# SiNEProduction.net
KiCad netlist of a schematic drawn in EAGLE
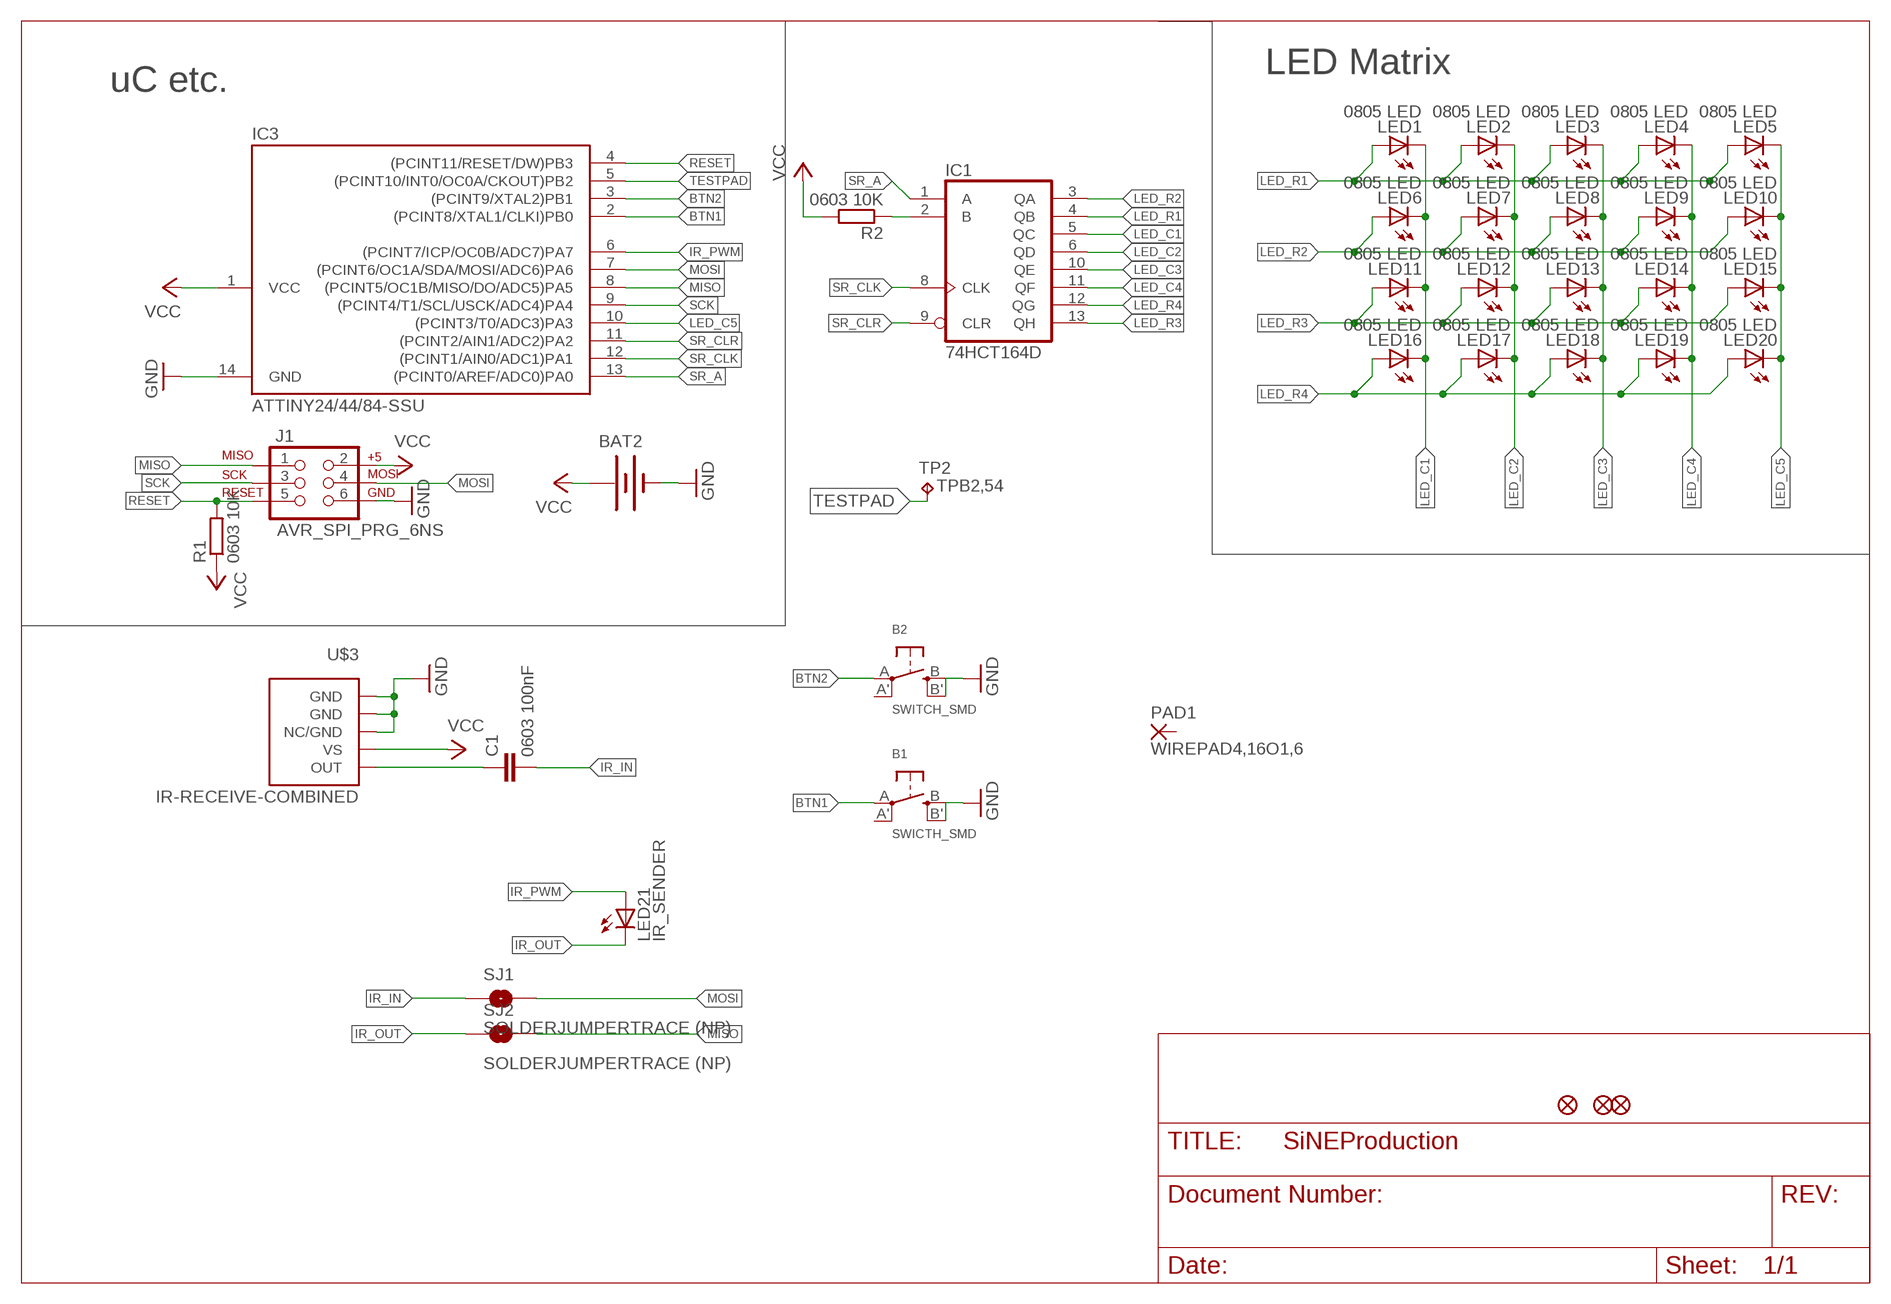
[diagram p0: schematic, sheet 1]

(export (version "E")
  (design (tool "Eeschema 10.0.6"))
  (components
    (comp (ref "B1")
      (value "SWICTH_SMD")
      (footprint "eagle-import:EVQ-Q2")
      (libsource (lib "eagle-import") (part "SWITCH_TACT_SMT"))
    )
    (comp (ref "B2")
      (value "SWITCH_SMD")
      (footprint "eagle-import:EVQ-Q2")
      (libsource (lib "eagle-import") (part "SWITCH_TACT_SMT"))
    )
    (comp (ref "BAT2")
      (value "BATTERY20SMD")
      (footprint "eagle-import:BATTCON_20MM")
      (libsource (lib "eagle-import") (part "BATTERY20SMD"))
    )
    (comp (ref "C1")
      (value "0603 100nF")
      (footprint "eagle-import:C0805")
      (libsource (lib "eagle-import") (part "C-EUC0805"))
    )
    (comp (ref "IC1")
      (value "74HCT164D")
      (footprint "eagle-import:SO14")
      (libsource (lib "eagle-import") (part "74164DHCT"))
    )
    (comp (ref "IC3")
      (value "ATTINY24/44/84-SSU")
      (footprint "eagle-import:SOIC14")
      (libsource (lib "eagle-import") (part "ATTINY24/44/84-SSU"))
    )
    (comp (ref "J1")
      (value "AVR_SPI_PRG_6NS")
      (footprint "eagle-import:2X3-NS")
      (libsource (lib "eagle-import") (part "AVR_SPI_PRG_6NS"))
    )
    (comp (ref "JP1")
      (value "FIDUCIAL1X2.5-STOP")
      (footprint "eagle-import:FIDUCIAL-1X2.5-STOP")
      (libsource (lib "eagle-import") (part "FIDUCIAL1X2.5-STOP"))
    )
    (comp (ref "JP2")
      (value "FIDUCIAL1X2.5-STOP")
      (footprint "eagle-import:FIDUCIAL-1X2.5-STOP")
      (libsource (lib "eagle-import") (part "FIDUCIAL1X2.5-STOP"))
    )
    (comp (ref "JP3")
      (value "FIDUCIAL1X2.5-STOP")
      (footprint "eagle-import:FIDUCIAL-1X2.5-STOP")
      (libsource (lib "eagle-import") (part "FIDUCIAL1X2.5-STOP"))
    )
    (comp (ref "LED1")
      (value "0805 LED")
      (footprint "eagle-import:CHIPLED_0805")
      (libsource (lib "eagle-import") (part "LEDCHIPLED_0805"))
    )
    (comp (ref "LED2")
      (value "0805 LED")
      (footprint "eagle-import:CHIPLED_0805")
      (libsource (lib "eagle-import") (part "LEDCHIPLED_0805"))
    )
    (comp (ref "LED3")
      (value "0805 LED")
      (footprint "eagle-import:CHIPLED_0805")
      (libsource (lib "eagle-import") (part "LEDCHIPLED_0805"))
    )
    (comp (ref "LED4")
      (value "0805 LED")
      (footprint "eagle-import:CHIPLED_0805")
      (libsource (lib "eagle-import") (part "LEDCHIPLED_0805"))
    )
    (comp (ref "LED5")
      (value "0805 LED")
      (footprint "eagle-import:CHIPLED_0805")
      (libsource (lib "eagle-import") (part "LEDCHIPLED_0805"))
    )
    (comp (ref "LED6")
      (value "0805 LED")
      (footprint "eagle-import:CHIPLED_0805")
      (libsource (lib "eagle-import") (part "LEDCHIPLED_0805"))
    )
    (comp (ref "LED7")
      (value "0805 LED")
      (footprint "eagle-import:CHIPLED_0805")
      (libsource (lib "eagle-import") (part "LEDCHIPLED_0805"))
    )
    (comp (ref "LED8")
      (value "0805 LED")
      (footprint "eagle-import:CHIPLED_0805")
      (libsource (lib "eagle-import") (part "LEDCHIPLED_0805"))
    )
    (comp (ref "LED9")
      (value "0805 LED")
      (footprint "eagle-import:CHIPLED_0805")
      (libsource (lib "eagle-import") (part "LEDCHIPLED_0805"))
    )
    (comp (ref "LED10")
      (value "0805 LED")
      (footprint "eagle-import:CHIPLED_0805")
      (libsource (lib "eagle-import") (part "LEDCHIPLED_0805"))
    )
    (comp (ref "LED11")
      (value "0805 LED")
      (footprint "eagle-import:CHIPLED_0805")
      (libsource (lib "eagle-import") (part "LEDCHIPLED_0805"))
    )
    (comp (ref "LED12")
      (value "0805 LED")
      (footprint "eagle-import:CHIPLED_0805")
      (libsource (lib "eagle-import") (part "LEDCHIPLED_0805"))
    )
    (comp (ref "LED13")
      (value "0805 LED")
      (footprint "eagle-import:CHIPLED_0805")
      (libsource (lib "eagle-import") (part "LEDCHIPLED_0805"))
    )
    (comp (ref "LED14")
      (value "0805 LED")
      (footprint "eagle-import:CHIPLED_0805")
      (libsource (lib "eagle-import") (part "LEDCHIPLED_0805"))
    )
    (comp (ref "LED15")
      (value "0805 LED")
      (footprint "eagle-import:CHIPLED_0805")
      (libsource (lib "eagle-import") (part "LEDCHIPLED_0805"))
    )
    (comp (ref "LED16")
      (value "0805 LED")
      (footprint "eagle-import:CHIPLED_0805")
      (libsource (lib "eagle-import") (part "LEDCHIPLED_0805"))
    )
    (comp (ref "LED17")
      (value "0805 LED")
      (footprint "eagle-import:CHIPLED_0805")
      (libsource (lib "eagle-import") (part "LEDCHIPLED_0805"))
    )
    (comp (ref "LED18")
      (value "0805 LED")
      (footprint "eagle-import:CHIPLED_0805")
      (libsource (lib "eagle-import") (part "LEDCHIPLED_0805"))
    )
    (comp (ref "LED19")
      (value "0805 LED")
      (footprint "eagle-import:CHIPLED_0805")
      (libsource (lib "eagle-import") (part "LEDCHIPLED_0805"))
    )
    (comp (ref "LED20")
      (value "0805 LED")
      (footprint "eagle-import:CHIPLED_0805")
      (libsource (lib "eagle-import") (part "LEDCHIPLED_0805"))
    )
    (comp (ref "LED21")
      (value "IR_SENDER")
      (footprint "eagle-import:CHIPLED_1206")
      (libsource (lib "eagle-import") (part "led_LEDCHIPLED_1206"))
    )
    (comp (ref "PAD1")
      (value "WIREPAD4,16O1,6")
      (footprint "eagle-import:4,16O1,6")
      (libsource (lib "eagle-import") (part "WIREPAD4,16O1,6"))
    )
    (comp (ref "R1")
      (value "0603 10K")
      (footprint "eagle-import:R0805")
      (libsource (lib "eagle-import") (part "R-EU_R0805"))
    )
    (comp (ref "R2")
      (value "0603 10K")
      (footprint "eagle-import:R0805")
      (libsource (lib "eagle-import") (part "R-EU_R0805"))
    )
    (comp (ref "SJ1")
      (value "SOLDERJUMPERTRACE (NP)")
      (footprint "eagle-import:SJ_2S-TRACE")
      (libsource (lib "eagle-import") (part "SOLDERJUMPERTRACE"))
    )
    (comp (ref "SJ2")
      (value "SOLDERJUMPERTRACE (NP)")
      (footprint "eagle-import:SJ_2S-TRACE")
      (libsource (lib "eagle-import") (part "SOLDERJUMPERTRACE"))
    )
    (comp (ref "TP2")
      (value "TPB2,54")
      (footprint "eagle-import:B2,54")
      (libsource (lib "eagle-import") (part "TPB2,54"))
    )
    (comp (ref "U$3")
      (value "IR-RECEIVE-COMBINED")
      (footprint "eagle-import:TSOP-COMBINED")
      (libsource (lib "eagle-import") (part "IR-RECEIVE-COMBINED"))
    )
  )
  (nets
    (net (code "1") (name "BTN1") (class "Default")
      (node (ref "B1") (pin "A") (pinfunction "P_A") (pintype "passive"))
      (node (ref "IC3") (pin "2") (pinfunction "(PCINT8/XTAL1/CLKI)PB0_2") (pintype "bidirectional"))
    )
    (net (code "2") (name "BTN2") (class "Default")
      (node (ref "B2") (pin "A") (pinfunction "P_A") (pintype "passive"))
      (node (ref "IC3") (pin "3") (pinfunction "(PCINT9/XTAL2)PB1_3") (pintype "bidirectional"))
    )
    (net (code "3") (name "GND") (class "Default")
      (node (ref "B1") (pin "B") (pinfunction "S_B") (pintype "passive"))
      (node (ref "B1") (pin "B'") (pinfunction "S1_B'") (pintype "passive"))
      (node (ref "B2") (pin "B") (pinfunction "S_B") (pintype "passive"))
      (node (ref "B2") (pin "B'") (pinfunction "S1_B'") (pintype "passive"))
      (node (ref "BAT2") (pin "2") (pinfunction "-_2") (pintype "power_in"))
      (node (ref "IC3") (pin "14") (pinfunction "GND_14") (pintype "power_in"))
      (node (ref "J1") (pin "6") (pinfunction "6_6") (pintype "passive"))
      (node (ref "U$3") (pin "1") (pinfunction "GND_1") (pintype "bidirectional"))
      (node (ref "U$3") (pin "2") (pinfunction "NC/GND_2") (pintype "bidirectional"))
      (node (ref "U$3") (pin "5") (pinfunction "GND_5") (pintype "bidirectional"))
    )
    (net (code "4") (name "IR_IN") (class "Default")
      (node (ref "C1") (pin "2") (pinfunction "2_2") (pintype "passive"))
      (node (ref "SJ1") (pin "1") (pinfunction "1_1") (pintype "passive"))
    )
    (net (code "5") (name "IR_OUT") (class "Default")
      (node (ref "LED21") (pin "C") (pinfunction "C_C") (pintype "passive"))
      (node (ref "SJ2") (pin "1") (pinfunction "1_1") (pintype "passive"))
    )
    (net (code "6") (name "IR_PWM") (class "Default")
      (node (ref "IC3") (pin "6") (pinfunction "(PCINT7/ICP/OC0B/ADC7)PA7_6") (pintype "bidirectional"))
      (node (ref "LED21") (pin "A") (pinfunction "A_A") (pintype "passive"))
    )
    (net (code "7") (name "LED_C1") (class "Default")
      (node (ref "IC1") (pin "5") (pinfunction "QC_5") (pintype "output"))
      (node (ref "LED1") (pin "C") (pinfunction "C_C") (pintype "passive"))
      (node (ref "LED11") (pin "C") (pinfunction "C_C") (pintype "passive"))
      (node (ref "LED16") (pin "C") (pinfunction "C_C") (pintype "passive"))
      (node (ref "LED6") (pin "C") (pinfunction "C_C") (pintype "passive"))
    )
    (net (code "8") (name "LED_C2") (class "Default")
      (node (ref "IC1") (pin "6") (pinfunction "QD_6") (pintype "output"))
      (node (ref "LED12") (pin "C") (pinfunction "C_C") (pintype "passive"))
      (node (ref "LED17") (pin "C") (pinfunction "C_C") (pintype "passive"))
      (node (ref "LED2") (pin "C") (pinfunction "C_C") (pintype "passive"))
      (node (ref "LED7") (pin "C") (pinfunction "C_C") (pintype "passive"))
    )
    (net (code "9") (name "LED_C3") (class "Default")
      (node (ref "IC1") (pin "10") (pinfunction "QE_10") (pintype "output"))
      (node (ref "LED13") (pin "C") (pinfunction "C_C") (pintype "passive"))
      (node (ref "LED18") (pin "C") (pinfunction "C_C") (pintype "passive"))
      (node (ref "LED3") (pin "C") (pinfunction "C_C") (pintype "passive"))
      (node (ref "LED8") (pin "C") (pinfunction "C_C") (pintype "passive"))
    )
    (net (code "10") (name "LED_C4") (class "Default")
      (node (ref "IC1") (pin "11") (pinfunction "QF_11") (pintype "output"))
      (node (ref "LED14") (pin "C") (pinfunction "C_C") (pintype "passive"))
      (node (ref "LED19") (pin "C") (pinfunction "C_C") (pintype "passive"))
      (node (ref "LED4") (pin "C") (pinfunction "C_C") (pintype "passive"))
      (node (ref "LED9") (pin "C") (pinfunction "C_C") (pintype "passive"))
    )
    (net (code "11") (name "LED_C5") (class "Default")
      (node (ref "IC3") (pin "10") (pinfunction "(PCINT3/T0/ADC3)PA3_10") (pintype "bidirectional"))
      (node (ref "LED10") (pin "C") (pinfunction "C_C") (pintype "passive"))
      (node (ref "LED15") (pin "C") (pinfunction "C_C") (pintype "passive"))
      (node (ref "LED20") (pin "C") (pinfunction "C_C") (pintype "passive"))
      (node (ref "LED5") (pin "C") (pinfunction "C_C") (pintype "passive"))
    )
    (net (code "12") (name "LED_R1") (class "Default")
      (node (ref "IC1") (pin "4") (pinfunction "QB_4") (pintype "output"))
      (node (ref "LED1") (pin "A") (pinfunction "A_A") (pintype "passive"))
      (node (ref "LED2") (pin "A") (pinfunction "A_A") (pintype "passive"))
      (node (ref "LED3") (pin "A") (pinfunction "A_A") (pintype "passive"))
      (node (ref "LED4") (pin "A") (pinfunction "A_A") (pintype "passive"))
      (node (ref "LED5") (pin "A") (pinfunction "A_A") (pintype "passive"))
    )
    (net (code "13") (name "LED_R2") (class "Default")
      (node (ref "IC1") (pin "3") (pinfunction "QA_3") (pintype "output"))
      (node (ref "LED10") (pin "A") (pinfunction "A_A") (pintype "passive"))
      (node (ref "LED6") (pin "A") (pinfunction "A_A") (pintype "passive"))
      (node (ref "LED7") (pin "A") (pinfunction "A_A") (pintype "passive"))
      (node (ref "LED8") (pin "A") (pinfunction "A_A") (pintype "passive"))
      (node (ref "LED9") (pin "A") (pinfunction "A_A") (pintype "passive"))
    )
    (net (code "14") (name "LED_R3") (class "Default")
      (node (ref "IC1") (pin "13") (pinfunction "QH_13") (pintype "output"))
      (node (ref "LED11") (pin "A") (pinfunction "A_A") (pintype "passive"))
      (node (ref "LED12") (pin "A") (pinfunction "A_A") (pintype "passive"))
      (node (ref "LED13") (pin "A") (pinfunction "A_A") (pintype "passive"))
      (node (ref "LED14") (pin "A") (pinfunction "A_A") (pintype "passive"))
      (node (ref "LED15") (pin "A") (pinfunction "A_A") (pintype "passive"))
    )
    (net (code "15") (name "LED_R4") (class "Default")
      (node (ref "IC1") (pin "12") (pinfunction "QG_12") (pintype "output"))
      (node (ref "LED16") (pin "A") (pinfunction "A_A") (pintype "passive"))
      (node (ref "LED17") (pin "A") (pinfunction "A_A") (pintype "passive"))
      (node (ref "LED18") (pin "A") (pinfunction "A_A") (pintype "passive"))
      (node (ref "LED19") (pin "A") (pinfunction "A_A") (pintype "passive"))
      (node (ref "LED20") (pin "A") (pinfunction "A_A") (pintype "passive"))
    )
    (net (code "16") (name "MISO") (class "Default")
      (node (ref "IC3") (pin "8") (pinfunction "(PCINT5/OC1B/MISO/DO/ADC5)PA5_8") (pintype "bidirectional"))
      (node (ref "J1") (pin "1") (pinfunction "1_1") (pintype "passive"))
      (node (ref "SJ2") (pin "2") (pinfunction "2_2") (pintype "passive"))
    )
    (net (code "17") (name "MOSI") (class "Default")
      (node (ref "IC3") (pin "7") (pinfunction "(PCINT6/OC1A/SDA/MOSI/ADC6)PA6_7") (pintype "bidirectional"))
      (node (ref "J1") (pin "4") (pinfunction "4_4") (pintype "passive"))
      (node (ref "SJ1") (pin "2") (pinfunction "2_2") (pintype "passive"))
    )
    (net (code "18") (name "Net-(IC1A-B)") (class "Default")
      (node (ref "IC1") (pin "2") (pinfunction "B_2") (pintype "input"))
      (node (ref "R2") (pin "1") (pinfunction "1_1") (pintype "passive"))
    )
    (net (code "19") (name "Net-(U$3-OUT)") (class "Default")
      (node (ref "C1") (pin "1") (pinfunction "1_1") (pintype "passive"))
      (node (ref "U$3") (pin "4") (pinfunction "OUT_4") (pintype "bidirectional"))
    )
    (net (code "20") (name "RESET") (class "Default")
      (node (ref "IC3") (pin "4") (pinfunction "(PCINT11/RESET/DW)PB3_4") (pintype "bidirectional"))
      (node (ref "J1") (pin "5") (pinfunction "5_5") (pintype "passive"))
      (node (ref "R1") (pin "2") (pinfunction "2_2") (pintype "passive"))
    )
    (net (code "21") (name "SCK") (class "Default")
      (node (ref "IC3") (pin "9") (pinfunction "(PCINT4/T1/SCL/USCK/ADC4)PA4_9") (pintype "bidirectional"))
      (node (ref "J1") (pin "3") (pinfunction "3_3") (pintype "passive"))
    )
    (net (code "22") (name "SR_A") (class "Default")
      (node (ref "IC1") (pin "1") (pinfunction "A_1") (pintype "input"))
      (node (ref "IC3") (pin "13") (pinfunction "(PCINT0/AREF/ADC0)PA0_13") (pintype "bidirectional"))
    )
    (net (code "23") (name "SR_CLK") (class "Default")
      (node (ref "IC1") (pin "8") (pinfunction "CLK_8") (pintype "input"))
      (node (ref "IC3") (pin "12") (pinfunction "(PCINT1/AIN0/ADC1)PA1_12") (pintype "bidirectional"))
    )
    (net (code "24") (name "SR_CLR") (class "Default")
      (node (ref "IC1") (pin "9") (pinfunction "CLR_9") (pintype "input"))
      (node (ref "IC3") (pin "11") (pinfunction "(PCINT2/AIN1/ADC2)PA2_11") (pintype "bidirectional"))
    )
    (net (code "25") (name "TESTPAD") (class "Default")
      (node (ref "IC3") (pin "5") (pinfunction "(PCINT10/INT0/OC0A/CKOUT)PB2_5") (pintype "bidirectional"))
      (node (ref "TP2") (pin "TP") (pinfunction "TP_TP") (pintype "input"))
    )
    (net (code "26") (name "VCC") (class "Default")
      (node (ref "BAT2") (pin "1") (pinfunction "+_1") (pintype "power_in"))
      (node (ref "IC3") (pin "1") (pinfunction "VCC_1") (pintype "power_in"))
      (node (ref "J1") (pin "2") (pinfunction "2_2") (pintype "passive"))
      (node (ref "R1") (pin "1") (pinfunction "1_1") (pintype "passive"))
      (node (ref "R2") (pin "2") (pinfunction "2_2") (pintype "passive"))
      (node (ref "U$3") (pin "3") (pinfunction "VS_3") (pintype "bidirectional"))
    )
    (net (code "27") (name "unconnected-(B1-P1-PadA')") (class "Default")
      (node (ref "B1") (pin "A'") (pinfunction "P1_A'") (pintype "passive"))
    )
    (net (code "28") (name "unconnected-(B2-P1-PadA')") (class "Default")
      (node (ref "B2") (pin "A'") (pinfunction "P1_A'") (pintype "passive"))
    )
    (net (code "29") (name "unconnected-(PAD1-P-Pad1)") (class "Default")
      (node (ref "PAD1") (pin "1") (pinfunction "P_1") (pintype "passive"))
    )
  )
)
